# gg-easyeda-pro-v1_1.net
KiCad netlist of a schematic drawn in EasyEDA Pro
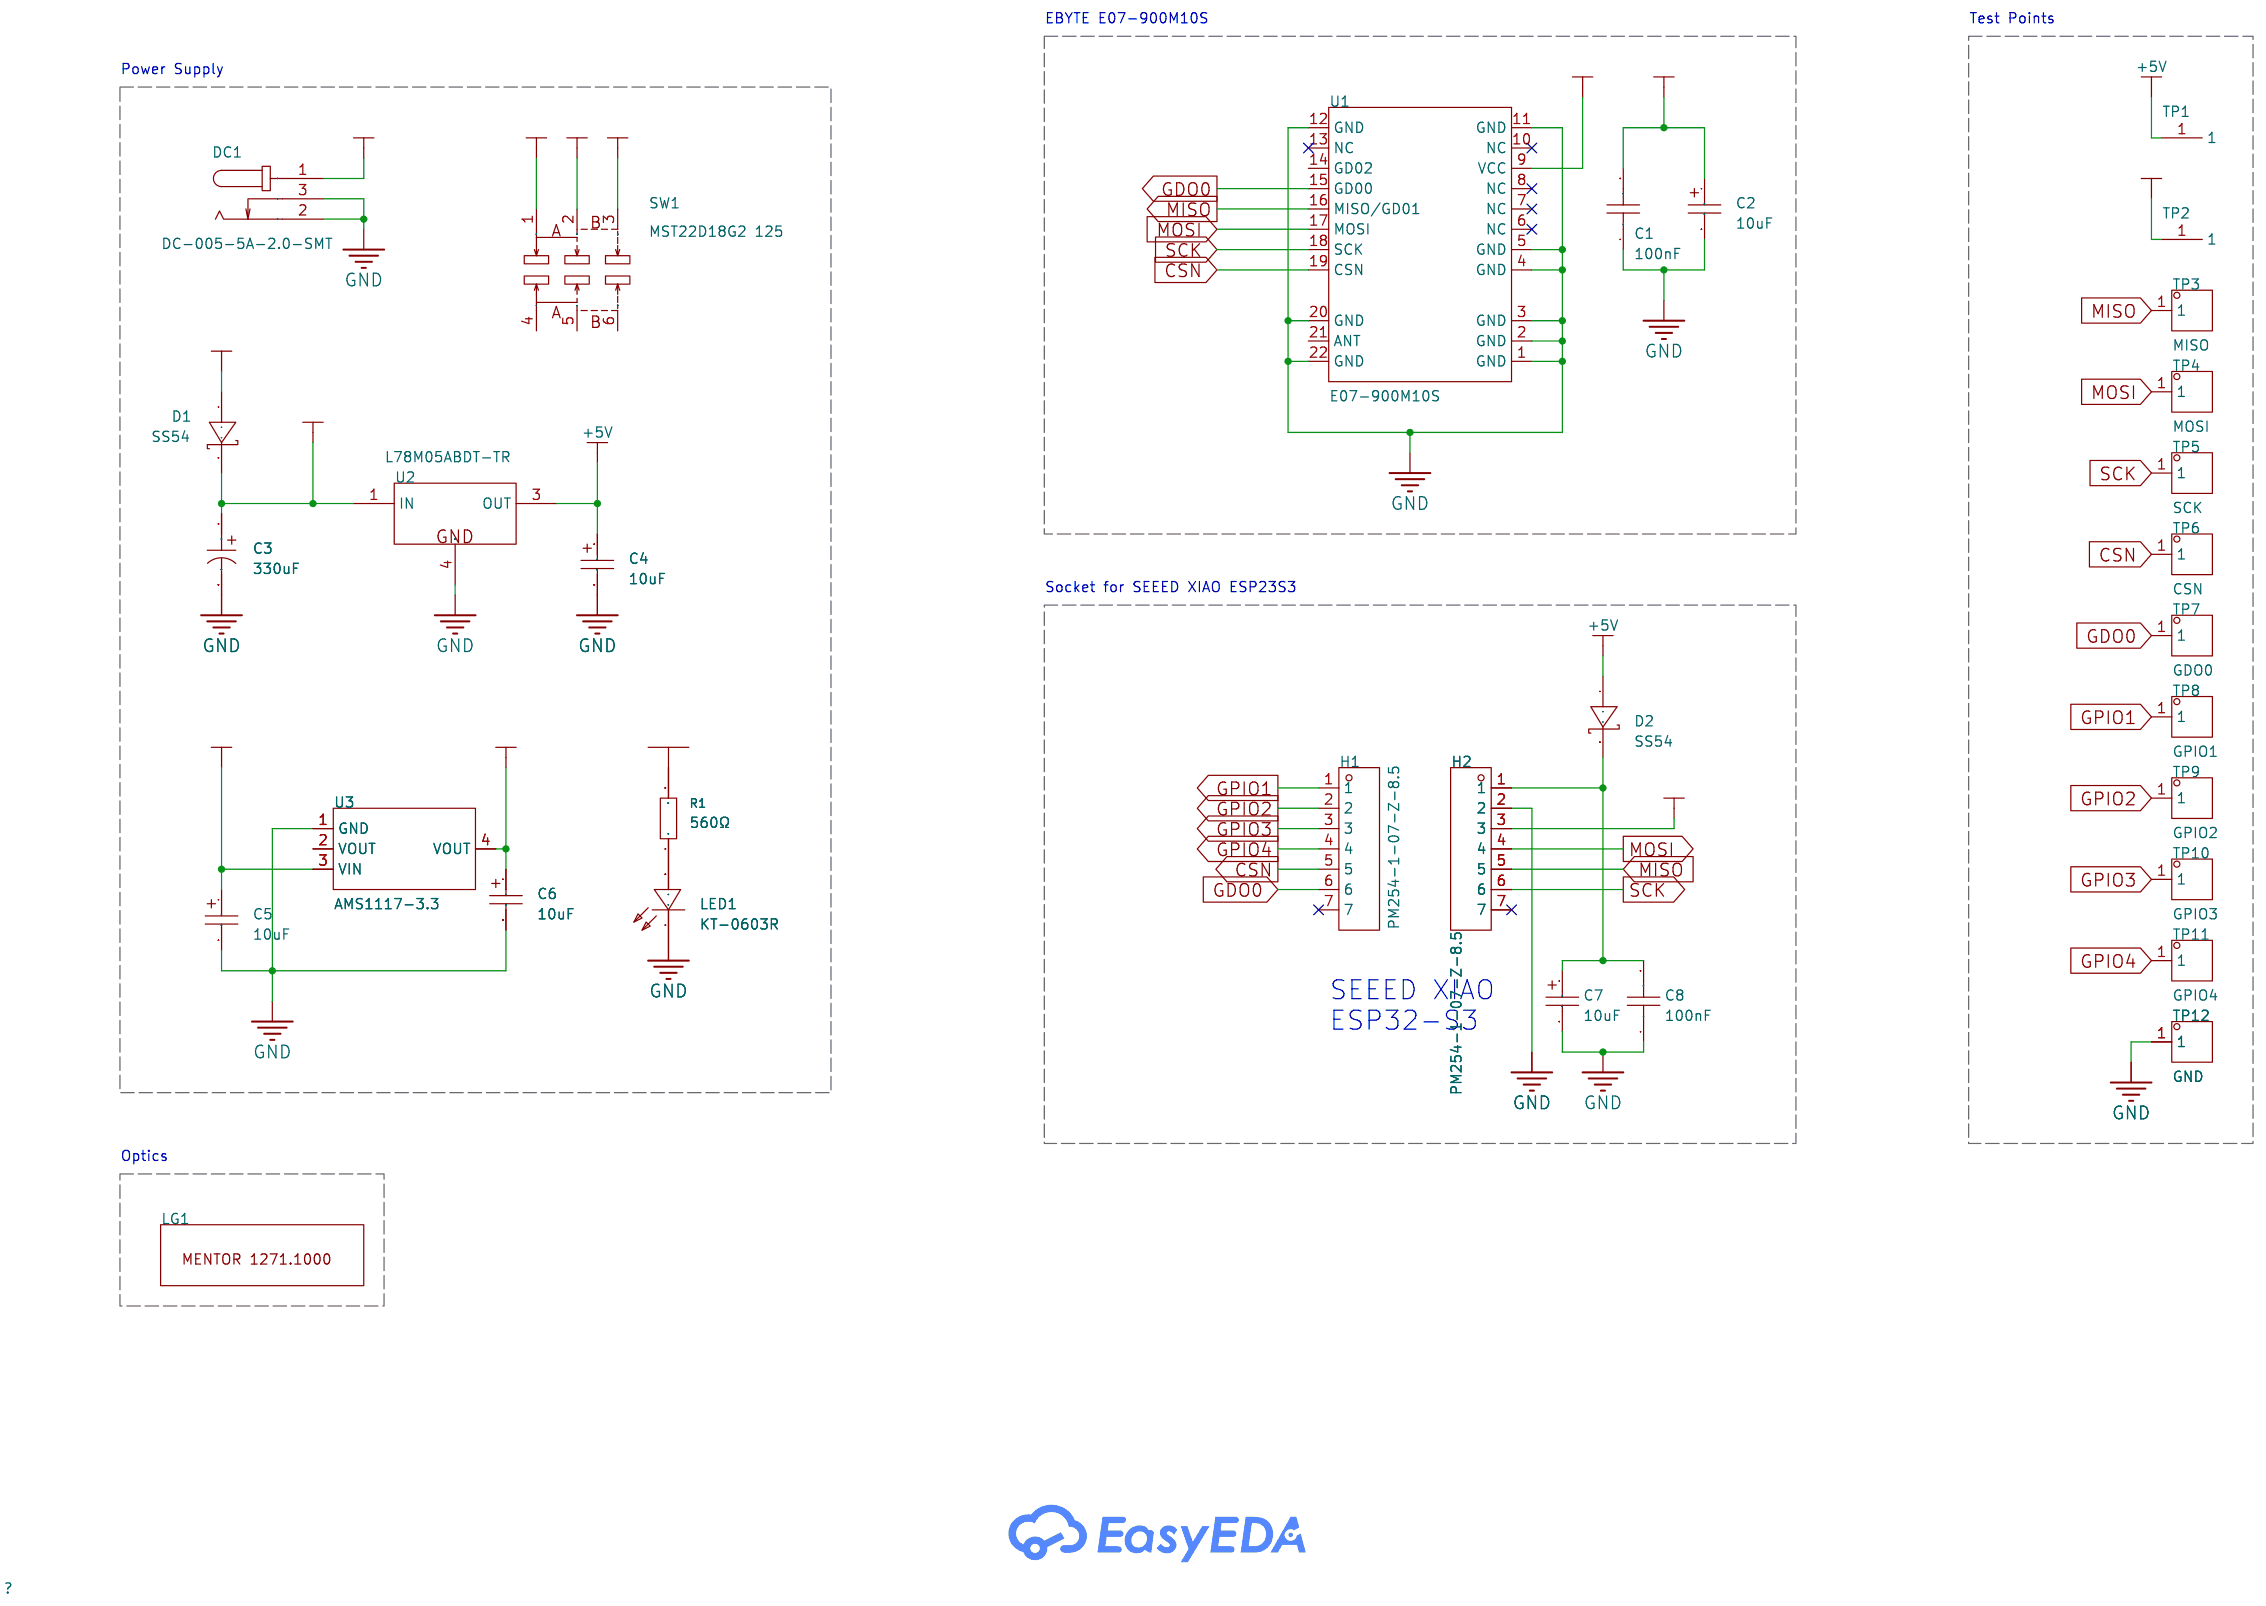
[diagram p0: schematic sheet]

(export (version "E")
  (design (tool "Eeschema 10.0.6"))
  (components
    (comp (ref "C1")
      (value "100nF")
      (footprint "easyedapro:C0805")
      (fields
        (field (name "Manufacturer Part") "CC0805KRX7R9BB104")
        (field (name "Manufacturer") "YAGEO(国巨)")
      )
      (libsource (lib "easyedapro") (part "CC0805KRX7R9BB104"))
    )
    (comp (ref "C2")
      (value "10uF")
      (footprint "easyedapro:CAP-SMD_L3.2-W1.6-RD-C7171")
      (fields (field (name "Manufacturer Part") "TAJA106K016RNJ") (field (name "Manufacturer") "Kyocera AVX"))
      (libsource (lib "easyedapro") (part "TAJA106K016RNJ"))
    )
    (comp (ref "C3")
      (value "330uF")
      (footprint "easyedapro:CAP-SMD_BD6.3-L6.6-W6.6-LS7.6-RD")
      (fields (field (name "Manufacturer Part") "189RV0016") (field (name "Manufacturer") "KNSCHA(科尼盛)"))
      (libsource (lib "easyedapro") (part "189RV0016"))
    )
    (comp (ref "C4")
      (value "10uF")
      (footprint "easyedapro:CAP-SMD_L3.2-W1.6-RD-C7171")
      (fields (field (name "Manufacturer Part") "TAJA106K016RNJ") (field (name "Manufacturer") "Kyocera AVX"))
      (libsource (lib "easyedapro") (part "TAJA106K016RNJ"))
    )
    (comp (ref "C5")
      (value "10uF")
      (footprint "easyedapro:CAP-SMD_L3.2-W1.6-RD-C7171")
      (fields (field (name "Manufacturer Part") "TAJA106K016RNJ") (field (name "Manufacturer") "Kyocera AVX"))
      (libsource (lib "easyedapro") (part "TAJA106K016RNJ"))
    )
    (comp (ref "C6")
      (value "10uF")
      (footprint "easyedapro:CAP-SMD_L3.2-W1.6-RD-C7171")
      (fields (field (name "Manufacturer Part") "TAJA106K016RNJ") (field (name "Manufacturer") "Kyocera AVX"))
      (libsource (lib "easyedapro") (part "TAJA106K016RNJ"))
    )
    (comp (ref "C7")
      (value "10uF")
      (footprint "easyedapro:CAP-SMD_L3.2-W1.6-RD-C7171")
      (fields (field (name "Manufacturer Part") "TAJA106K016RNJ") (field (name "Manufacturer") "Kyocera AVX"))
      (libsource (lib "easyedapro") (part "TAJA106K016RNJ"))
    )
    (comp (ref "C8")
      (value "100nF")
      (footprint "easyedapro:C0805")
      (fields
        (field (name "Manufacturer Part") "CC0805KRX7R9BB104")
        (field (name "Manufacturer") "YAGEO(国巨)")
      )
      (libsource (lib "easyedapro") (part "CC0805KRX7R9BB104"))
    )
    (comp (ref "D1")
      (value "SS54")
      (footprint "easyedapro:SMA_L4.4-W2.8-LS5.4-R-RD")
      (fields (field (name "Manufacturer") "MDD(辰达半导体)"))
      (libsource (lib "easyedapro") (part "SS54_C22452"))
    )
    (comp (ref "D2")
      (value "SS54")
      (footprint "easyedapro:SMA_L4.4-W2.8-LS5.4-R-RD")
      (fields (field (name "Manufacturer") "MDD(辰达半导体)"))
      (libsource (lib "easyedapro") (part "SS54_C22452"))
    )
    (comp (ref "DC1")
      (value "DC-005-5A-2.0-SMT")
      (footprint "easyedapro:DC-IN-TH_DC-005-5A-2.0-SMT")
      (fields (field (name "Manufacturer") "XKB Connection(中国星坤)"))
      (libsource (lib "easyedapro") (part "DC-005-5A-2.0-SMT"))
    )
    (comp (ref "H1")
      (value "PM254-1-07-Z-8.5")
      (footprint "easyedapro:HDR-TH_7P-P2.54-V-F")
      (fields (field (name "Manufacturer") "HCTL(华灿天禄)"))
      (libsource (lib "easyedapro") (part "PM254-1-07-Z-8.5"))
    )
    (comp (ref "H2")
      (value "PM254-1-07-Z-8.5")
      (footprint "easyedapro:HDR-TH_7P-P2.54-V-F")
      (fields (field (name "Manufacturer") "HCTL(华灿天禄)"))
      (libsource (lib "easyedapro") (part "PM254-1-07-Z-8.5"))
    )
    (comp (ref "LED1")
      (value "KT-0603R")
      (footprint "easyedapro:LED0603-RD")
      (fields (field (name "Manufacturer") "KENTO"))
      (libsource (lib "easyedapro") (part "KT-0603R"))
    )
    (comp (ref "LG1")
      (value "~")
      (footprint "easyedapro:MENTOR-1271.1000")
      (description "MENTOR 1271.1000")
      (libsource (lib "easyedapro") (part "Lightguide 1"))
    )
    (comp (ref "R1")
      (value "560Ω")
      (footprint "easyedapro:R0603")
      (fields
        (field (name "Manufacturer Part") "0603WAF5600T5E")
        (field (name "Manufacturer") "UNI-ROYAL(厚声)")
      )
      (libsource (lib "easyedapro") (part "0603WAF5600T5E"))
    )
    (comp (ref "SW1")
      (value "MST22D18G2 125")
      (footprint "easyedapro:SW-SMD_MST22D18G2")
      (fields (field (name "Manufacturer") "SHOU HAN(首韩)"))
      (libsource (lib "easyedapro") (part "MST22D18G2 125"))
    )
    (comp (ref "TP1")
      (value "+5V")
      (footprint "easyedapro:Testpoint_SMD_R1.5_Border")
      (libsource (lib "easyedapro") (part "Testpoint1"))
    )
    (comp (ref "TP2")
      (value "3V3")
      (footprint "easyedapro:Testpoint_SMD_R1.5_Border")
      (libsource (lib "easyedapro") (part "Testpoint1"))
    )
    (comp (ref "TP3")
      (value "MISO")
      (footprint "easyedapro:TEST-TH_BD2.54-P1.39")
      (fields (field (name "Manufacturer Part") "5001") (field (name "Manufacturer") "Keystone"))
      (libsource (lib "easyedapro") (part "5001"))
    )
    (comp (ref "TP4")
      (value "MOSI")
      (footprint "easyedapro:TEST-TH_BD2.54-P1.39")
      (fields (field (name "Manufacturer Part") "5001") (field (name "Manufacturer") "Keystone"))
      (libsource (lib "easyedapro") (part "5001"))
    )
    (comp (ref "TP5")
      (value "SCK")
      (footprint "easyedapro:TEST-TH_BD2.54-P1.39")
      (fields (field (name "Manufacturer Part") "5001") (field (name "Manufacturer") "Keystone"))
      (libsource (lib "easyedapro") (part "5001"))
    )
    (comp (ref "TP6")
      (value "CSN")
      (footprint "easyedapro:TEST-TH_BD2.54-P1.39")
      (fields (field (name "Manufacturer Part") "5001") (field (name "Manufacturer") "Keystone"))
      (libsource (lib "easyedapro") (part "5001"))
    )
    (comp (ref "TP7")
      (value "GDO0")
      (footprint "easyedapro:TEST-TH_BD2.54-P1.39")
      (fields (field (name "Manufacturer Part") "5001") (field (name "Manufacturer") "Keystone"))
      (libsource (lib "easyedapro") (part "5001"))
    )
    (comp (ref "TP8")
      (value "GPIO1")
      (footprint "easyedapro:TEST-TH_BD2.54-P1.39")
      (fields (field (name "Manufacturer Part") "5001") (field (name "Manufacturer") "Keystone"))
      (libsource (lib "easyedapro") (part "5001"))
    )
    (comp (ref "TP9")
      (value "GPIO2")
      (footprint "easyedapro:TEST-TH_BD2.54-P1.39")
      (fields (field (name "Manufacturer Part") "5001") (field (name "Manufacturer") "Keystone"))
      (libsource (lib "easyedapro") (part "5001"))
    )
    (comp (ref "TP10")
      (value "GPIO3")
      (footprint "easyedapro:TEST-TH_BD2.54-P1.39")
      (fields (field (name "Manufacturer Part") "5001") (field (name "Manufacturer") "Keystone"))
      (libsource (lib "easyedapro") (part "5001"))
    )
    (comp (ref "TP11")
      (value "GPIO4")
      (footprint "easyedapro:TEST-TH_BD2.54-P1.39")
      (fields (field (name "Manufacturer Part") "5001") (field (name "Manufacturer") "Keystone"))
      (libsource (lib "easyedapro") (part "5001"))
    )
    (comp (ref "TP12")
      (value "GND")
      (footprint "easyedapro:TEST-TH_BD2.54-P1.39")
      (fields (field (name "Manufacturer Part") "5001") (field (name "Manufacturer") "Keystone"))
      (libsource (lib "easyedapro") (part "5001"))
    )
    (comp (ref "U1")
      (value "E07-900M10S")
      (footprint "easyedapro:WIRELM-SMD_22P-L20.0-W14.0-P1.27-BR")
      (libsource (lib "easyedapro") (part "E07-900M10S"))
    )
    (comp (ref "U2")
      (value "L78M05ABDT-TR")
      (footprint "easyedapro:TO-252-2_L6.5-W6.1-P4.58-LS10.0-TL")
      (fields (field (name "Manufacturer") "ST(意法半导体)"))
      (libsource (lib "easyedapro") (part "L78M05ABDT-TR"))
    )
    (comp (ref "U3")
      (value "AMS1117-3.3")
      (footprint "easyedapro:SOT-223-3_L6.5-W3.4-P2.30-LS7.0-BR")
      (fields (field (name "Manufacturer") "AMS"))
      (libsource (lib "easyedapro") (part "AMS1117-3.3"))
    )
  )
  (nets
    (net (code "1") (name "+3V3") (class "Default")
      (node (ref "C1") (pin "2") (pinfunction "2_2") (pintype "unspecified"))
      (node (ref "C2") (pin "1") (pinfunction "1_1") (pintype "input"))
      (node (ref "R1") (pin "2") (pinfunction "2_2") (pintype "input"))
      (node (ref "SW1") (pin "2") (pinfunction "2_2") (pintype "unspecified"))
      (node (ref "TP2") (pin "1") (pinfunction "1_1") (pintype "input"))
      (node (ref "U1") (pin "9") (pinfunction "VCC_9") (pintype "unspecified"))
    )
    (net (code "2") (name "+3V3-LDO") (class "Default")
      (node (ref "C6") (pin "1") (pinfunction "1_1") (pintype "input"))
      (node (ref "SW1") (pin "1") (pinfunction "1_1") (pintype "unspecified"))
      (node (ref "U3") (pin "4") (pinfunction "VOUT_4") (pintype "unspecified"))
    )
    (net (code "3") (name "+3V3-XIAO") (class "Default")
      (node (ref "H2") (pin "3") (pinfunction "3_3") (pintype "unspecified"))
      (node (ref "SW1") (pin "3") (pinfunction "3_3") (pintype "unspecified"))
    )
    (net (code "4") (name "+5V") (class "Default")
      (node (ref "C4") (pin "1") (pinfunction "1_1") (pintype "input"))
      (node (ref "C5") (pin "1") (pinfunction "1_1") (pintype "input"))
      (node (ref "D2") (pin "1") (pinfunction "A_1") (pintype "unspecified"))
      (node (ref "TP1") (pin "1") (pinfunction "1_1") (pintype "input"))
      (node (ref "U2") (pin "3") (pinfunction "OUT_3") (pintype "unspecified"))
      (node (ref "U3") (pin "3") (pinfunction "VIN_3") (pintype "unspecified"))
    )
    (net (code "5") (name "+12V") (class "Default")
      (node (ref "C3") (pin "1") (pinfunction "1_1") (pintype "input"))
      (node (ref "D1") (pin "2") (pinfunction "K_2") (pintype "unspecified"))
      (node (ref "U2") (pin "1") (pinfunction "IN_1") (pintype "unspecified"))
    )
    (net (code "6") (name "+12V_IN") (class "Default")
      (node (ref "D1") (pin "1") (pinfunction "A_1") (pintype "unspecified"))
      (node (ref "DC1") (pin "1") (pinfunction "1_1") (pintype "unspecified"))
    )
    (net (code "7") (name "CSN") (class "Default")
      (node (ref "H1") (pin "5") (pinfunction "5_5") (pintype "unspecified"))
      (node (ref "TP6") (pin "1") (pinfunction "1_1") (pintype "unspecified"))
      (node (ref "U1") (pin "19") (pinfunction "CSN_19") (pintype "unspecified"))
    )
    (net (code "8") (name "GDO0") (class "Default")
      (node (ref "H1") (pin "6") (pinfunction "6_6") (pintype "unspecified"))
      (node (ref "TP7") (pin "1") (pinfunction "1_1") (pintype "unspecified"))
      (node (ref "U1") (pin "15") (pinfunction "GD00_15") (pintype "unspecified"))
    )
    (net (code "9") (name "GND") (class "Default")
      (node (ref "C1") (pin "1") (pinfunction "1_1") (pintype "unspecified"))
      (node (ref "C2") (pin "2") (pinfunction "2_2") (pintype "input"))
      (node (ref "C3") (pin "2") (pinfunction "2_2") (pintype "input"))
      (node (ref "C4") (pin "2") (pinfunction "2_2") (pintype "input"))
      (node (ref "C5") (pin "2") (pinfunction "2_2") (pintype "input"))
      (node (ref "C6") (pin "2") (pinfunction "2_2") (pintype "input"))
      (node (ref "C7") (pin "2") (pinfunction "2_2") (pintype "input"))
      (node (ref "C8") (pin "1") (pinfunction "1_1") (pintype "unspecified"))
      (node (ref "DC1") (pin "2") (pinfunction "2_2") (pintype "unspecified"))
      (node (ref "DC1") (pin "3") (pinfunction "3_3") (pintype "unspecified"))
      (node (ref "H2") (pin "2") (pinfunction "2_2") (pintype "unspecified"))
      (node (ref "LED1") (pin "1") (pinfunction "K_1") (pintype "unspecified"))
      (node (ref "TP12") (pin "1") (pinfunction "1_1") (pintype "unspecified"))
      (node (ref "U1") (pin "1") (pinfunction "GND_1") (pintype "unspecified"))
      (node (ref "U1") (pin "11") (pinfunction "GND_11") (pintype "unspecified"))
      (node (ref "U1") (pin "12") (pinfunction "GND_12") (pintype "unspecified"))
      (node (ref "U1") (pin "2") (pinfunction "GND_2") (pintype "unspecified"))
      (node (ref "U1") (pin "20") (pinfunction "GND_20") (pintype "unspecified"))
      (node (ref "U1") (pin "22") (pinfunction "GND_22") (pintype "unspecified"))
      (node (ref "U1") (pin "3") (pinfunction "GND_3") (pintype "unspecified"))
      (node (ref "U1") (pin "4") (pinfunction "GND_4") (pintype "unspecified"))
      (node (ref "U1") (pin "5") (pinfunction "GND_5") (pintype "unspecified"))
      (node (ref "U2") (pin "4") (pinfunction "GND_4") (pintype "unspecified"))
      (node (ref "U3") (pin "1") (pinfunction "GND_1") (pintype "unspecified"))
    )
    (net (code "10") (name "GPIO1") (class "Default")
      (node (ref "H1") (pin "1") (pinfunction "1_1") (pintype "unspecified"))
      (node (ref "TP8") (pin "1") (pinfunction "1_1") (pintype "unspecified"))
    )
    (net (code "11") (name "GPIO2") (class "Default")
      (node (ref "H1") (pin "2") (pinfunction "2_2") (pintype "unspecified"))
      (node (ref "TP9") (pin "1") (pinfunction "1_1") (pintype "unspecified"))
    )
    (net (code "12") (name "GPIO3") (class "Default")
      (node (ref "H1") (pin "3") (pinfunction "3_3") (pintype "unspecified"))
      (node (ref "TP10") (pin "1") (pinfunction "1_1") (pintype "unspecified"))
    )
    (net (code "13") (name "GPIO4") (class "Default")
      (node (ref "H1") (pin "4") (pinfunction "4_4") (pintype "unspecified"))
      (node (ref "TP11") (pin "1") (pinfunction "1_1") (pintype "unspecified"))
    )
    (net (code "14") (name "MISO") (class "Default")
      (node (ref "H2") (pin "5") (pinfunction "5_5") (pintype "unspecified"))
      (node (ref "TP3") (pin "1") (pinfunction "1_1") (pintype "unspecified"))
      (node (ref "U1") (pin "16") (pinfunction "MISO/GD01_16") (pintype "unspecified"))
    )
    (net (code "15") (name "MOSI") (class "Default")
      (node (ref "H2") (pin "4") (pinfunction "4_4") (pintype "unspecified"))
      (node (ref "TP4") (pin "1") (pinfunction "1_1") (pintype "unspecified"))
      (node (ref "U1") (pin "17") (pinfunction "MOSI_17") (pintype "unspecified"))
    )
    (net (code "16") (name "Net-(D2-K)") (class "Default")
      (node (ref "C7") (pin "1") (pinfunction "1_1") (pintype "input"))
      (node (ref "C8") (pin "2") (pinfunction "2_2") (pintype "unspecified"))
      (node (ref "D2") (pin "2") (pinfunction "K_2") (pintype "unspecified"))
      (node (ref "H2") (pin "1") (pinfunction "1_1") (pintype "unspecified"))
    )
    (net (code "17") (name "Net-(LED1-A)") (class "Default")
      (node (ref "LED1") (pin "2") (pinfunction "A_2") (pintype "unspecified"))
      (node (ref "R1") (pin "1") (pinfunction "1_1") (pintype "input"))
    )
    (net (code "18") (name "SCK") (class "Default")
      (node (ref "H2") (pin "6") (pinfunction "6_6") (pintype "unspecified"))
      (node (ref "TP5") (pin "1") (pinfunction "1_1") (pintype "unspecified"))
      (node (ref "U1") (pin "18") (pinfunction "SCK_18") (pintype "unspecified"))
    )
    (net (code "19") (name "unconnected-(H1-Pad7)") (class "Default")
      (node (ref "H1") (pin "7") (pinfunction "7_7") (pintype "unspecified+no_connect"))
    )
    (net (code "20") (name "unconnected-(H2-Pad7)") (class "Default")
      (node (ref "H2") (pin "7") (pinfunction "7_7") (pintype "unspecified+no_connect"))
    )
    (net (code "21") (name "unconnected-(SW1-Pad4)") (class "Default")
      (node (ref "SW1") (pin "4") (pinfunction "4_4") (pintype "unspecified"))
    )
    (net (code "22") (name "unconnected-(SW1-Pad5)") (class "Default")
      (node (ref "SW1") (pin "5") (pinfunction "5_5") (pintype "unspecified"))
    )
    (net (code "23") (name "unconnected-(SW1-Pad6)") (class "Default")
      (node (ref "SW1") (pin "6") (pinfunction "6_6") (pintype "unspecified"))
    )
    (net (code "24") (name "unconnected-(U1-ANT-Pad21)") (class "Default")
      (node (ref "U1") (pin "21") (pinfunction "ANT_21") (pintype "unspecified"))
    )
    (net (code "25") (name "unconnected-(U1-GD02-Pad14)") (class "Default")
      (node (ref "U1") (pin "14") (pinfunction "GD02_14") (pintype "unspecified"))
    )
    (net (code "26") (name "unconnected-(U1-NC-Pad6)") (class "Default")
      (node (ref "U1") (pin "6") (pinfunction "NC_6") (pintype "unspecified+no_connect"))
    )
    (net (code "27") (name "unconnected-(U1-NC-Pad7)") (class "Default")
      (node (ref "U1") (pin "7") (pinfunction "NC_7") (pintype "unspecified+no_connect"))
    )
    (net (code "28") (name "unconnected-(U1-NC-Pad8)") (class "Default")
      (node (ref "U1") (pin "8") (pinfunction "NC_8") (pintype "unspecified+no_connect"))
    )
    (net (code "29") (name "unconnected-(U1-NC-Pad10)") (class "Default")
      (node (ref "U1") (pin "10") (pinfunction "NC_10") (pintype "unspecified+no_connect"))
    )
    (net (code "30") (name "unconnected-(U1-NC-Pad13)") (class "Default")
      (node (ref "U1") (pin "13") (pinfunction "NC_13") (pintype "unspecified+no_connect"))
    )
    (net (code "31") (name "unconnected-(U3-VOUT-Pad2)") (class "Default")
      (node (ref "U3") (pin "2") (pinfunction "VOUT_2") (pintype "unspecified"))
    )
  )
)
